# LORA.net
KiCad netlist of a schematic drawn in Altium Designer
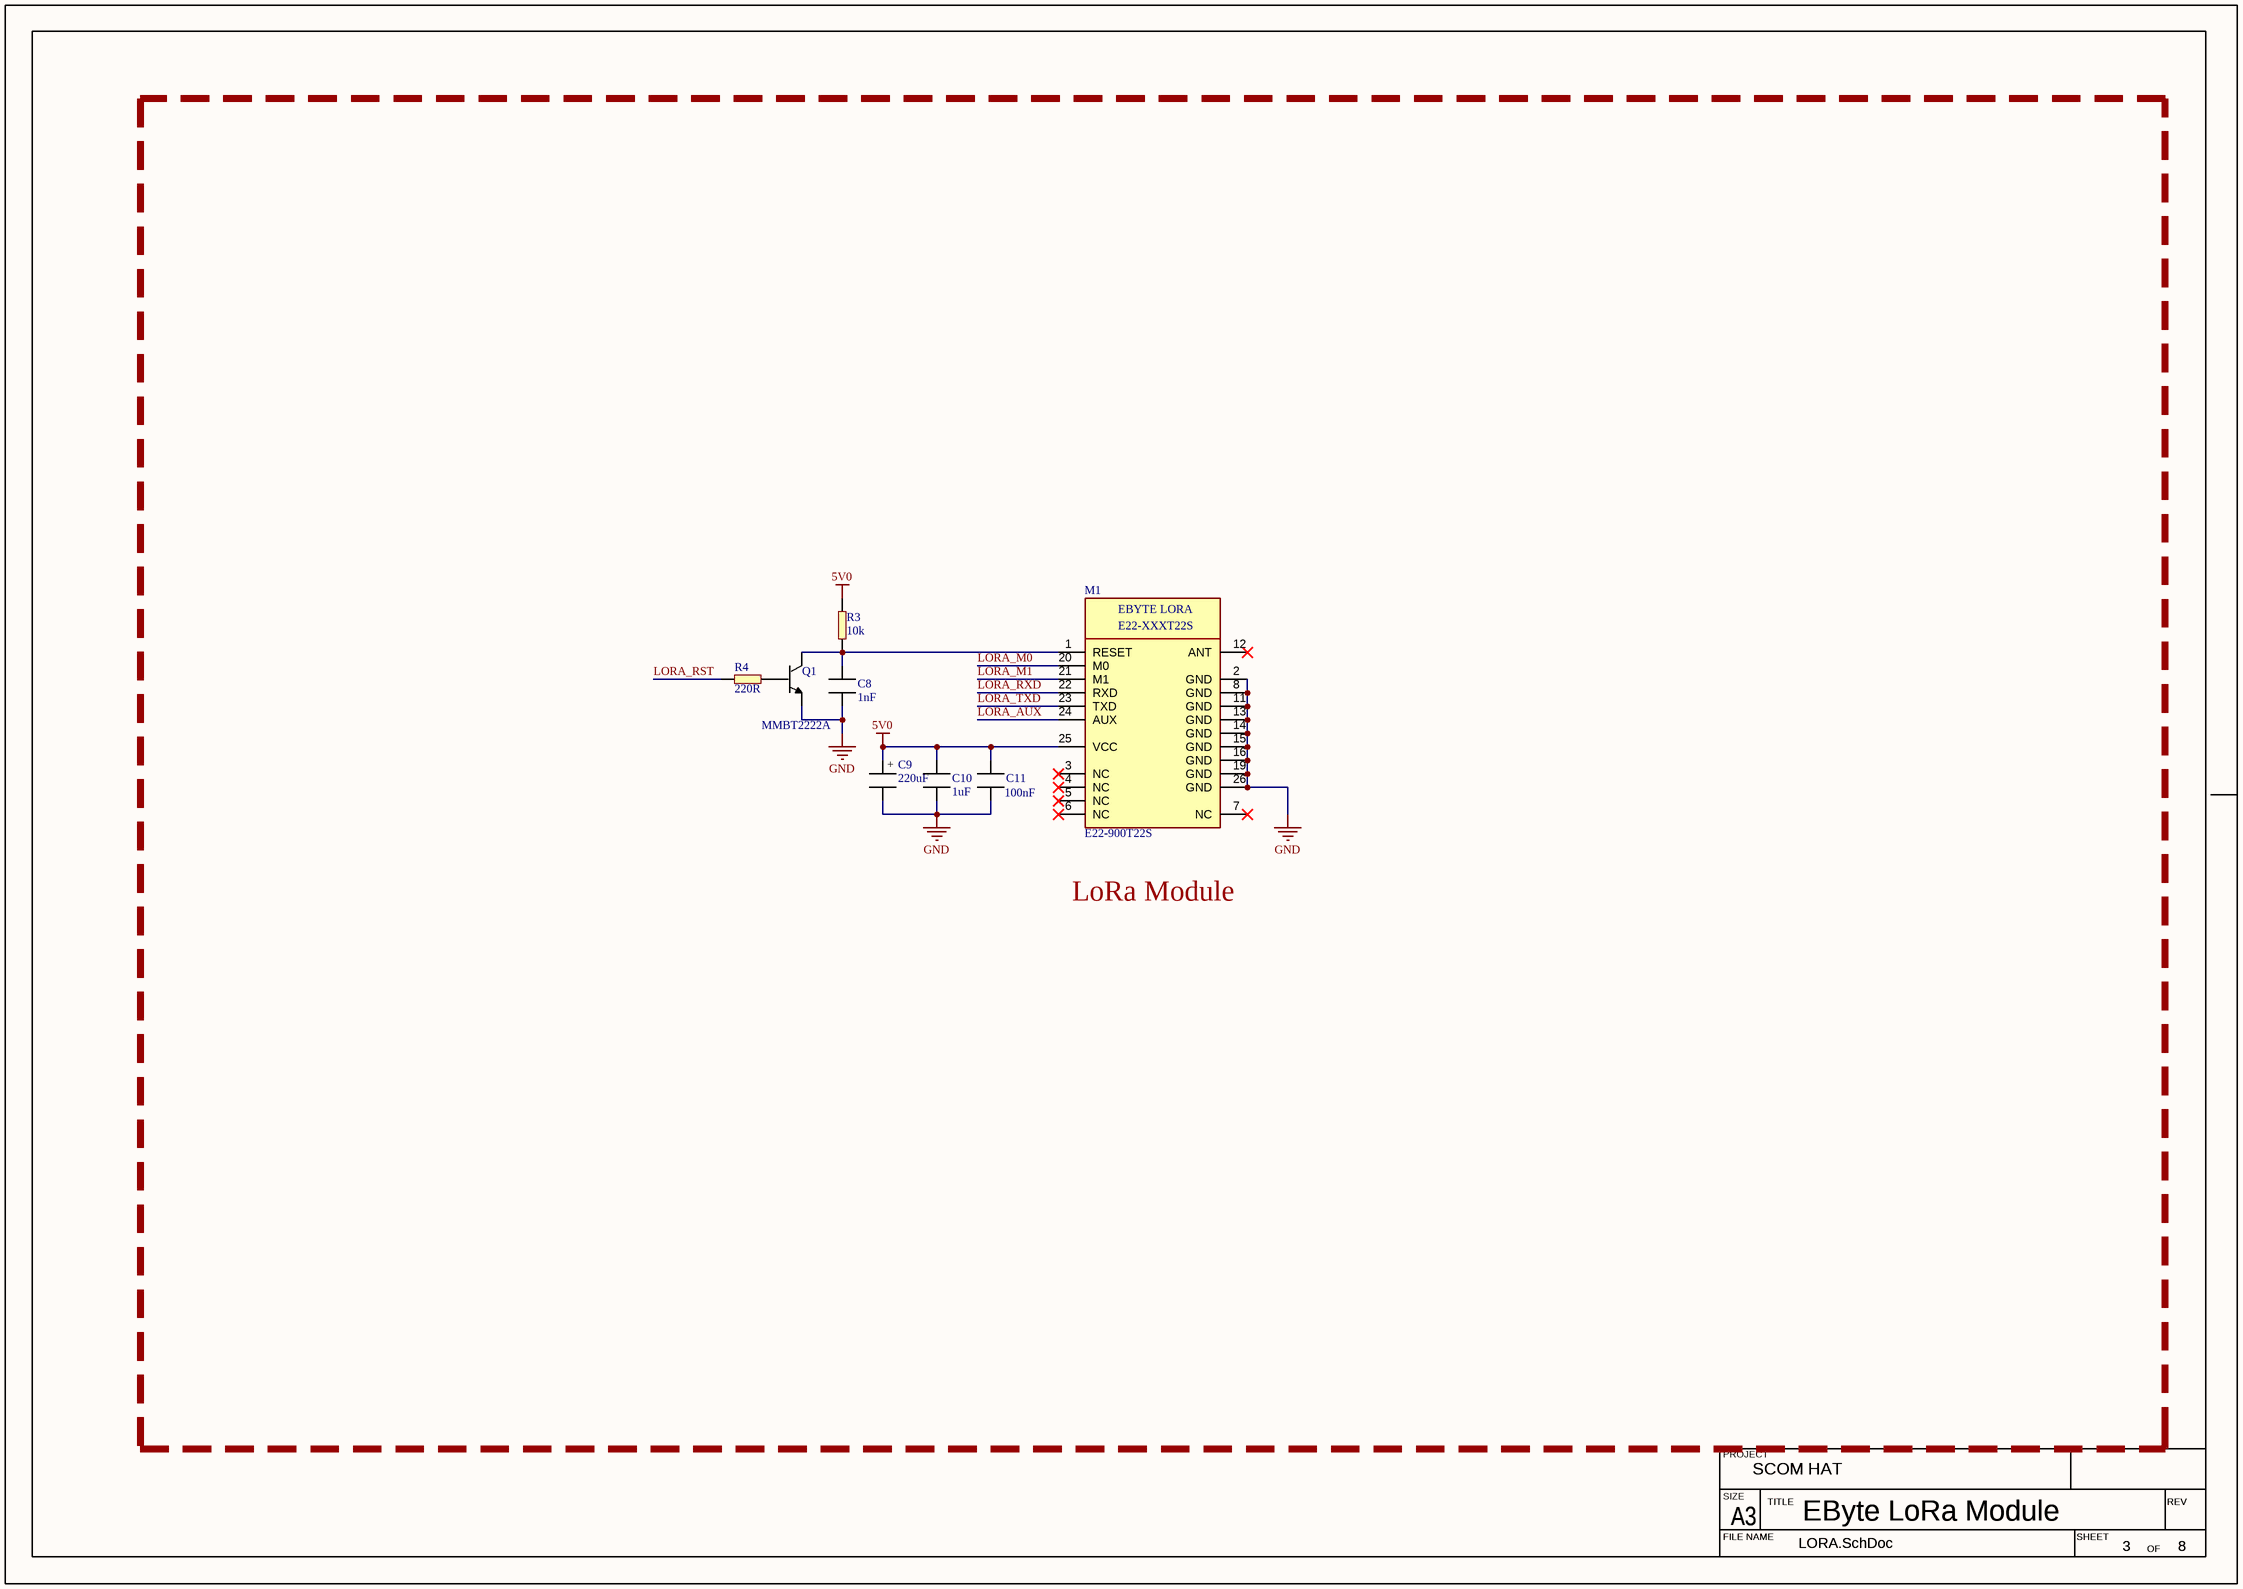
[diagram p0: LORA.SchDoc]

(export (version "E")
  (design (tool "Eeschema 10.0.6"))
  (components
    (comp (ref "C8")
      (value "1nF")
      (footprint "CAPC2012X13L")
      (description "Chip Capacitor, 2-Leads, Body 2.00x1.25mm, IPC High Density")
      (fields (field (name "Comment") "MLCC_0805"))
      (libsource (lib "Capacitor") (part "MLCC_0805"))
    )
    (comp (ref "C9")
      (value "220uF")
      (footprint "CAP_D10_H16_P5 - Flat")
      (description "Electrolytic Capacitor Through Hole D10 P5.0")
      (fields (field (name "Comment") "ERP_102-2"))
      (libsource (lib "ElectrolyticCapacitor") (part "CAP_D10_H16_P5"))
    )
    (comp (ref "C10")
      (value "1uF")
      (footprint "CAPC2012X13L")
      (description "Chip Capacitor, 2-Leads, Body 2.00x1.25mm, IPC High Density")
      (fields (field (name "Comment") "MLCC_0805"))
      (libsource (lib "Capacitor") (part "MLCC_0805"))
    )
    (comp (ref "C11")
      (value "100nF")
      (footprint "CAPC2012X13L")
      (description "Chip Capacitor, 2-Leads, Body 2.00x1.25mm, IPC High Density")
      (fields (field (name "Comment") "MLCC_0805"))
      (libsource (lib "Capacitor") (part "MLCC_0805"))
    )
    (comp (ref "M1")
      (value "E22-900T22S")
      (footprint "E22-XXXT22S")
      (description "E22 EByte LoRa Module")
      (fields (field (name "Comment") "E22-XXXT22S"))
      (libsource (lib "WirelessModule") (part "E22-XXXT22S"))
    )
    (comp (ref "Q1")
      (value "MMBT2222A")
      (footprint "MMBT2222")
      (fields (field (name "Comment") "ERP_105-1"))
      (libsource (lib "BJT") (part "MMBT2222"))
    )
    (comp (ref "R3")
      (value "10k")
      (footprint "RES_0603")
      (description "RES_0603")
      (fields (field (name "Comment") "ERP_101-1"))
      (libsource (lib "") (part "RES_0603_1"))
    )
    (comp (ref "R4")
      (value "220R")
      (footprint "RES_0603")
      (description "RES_0603")
      (fields (field (name "Comment") "ERP_101-1"))
      (libsource (lib "Resistor") (part "RES_0603"))
    )
  )
  (nets
    (net (code "1") (name "/LORA_AUX") (class "Default")
      (node (ref "M1") (pin "24") (pinfunction "AUX_24") (pintype "passive"))
    )
    (net (code "2") (name "/LORA_M0") (class "Default")
      (node (ref "M1") (pin "20") (pinfunction "M0_20") (pintype "passive"))
    )
    (net (code "3") (name "/LORA_M1") (class "Default")
      (node (ref "M1") (pin "21") (pinfunction "M1_21") (pintype "passive"))
    )
    (net (code "4") (name "/LORA_RST") (class "Default")
      (node (ref "R4") (pin "2") (pinfunction "2_2") (pintype "passive"))
    )
    (net (code "5") (name "/LORA_RXD") (class "Default")
      (node (ref "M1") (pin "22") (pinfunction "RXD_22") (pintype "passive"))
    )
    (net (code "6") (name "/LORA_TXD") (class "Default")
      (node (ref "M1") (pin "23") (pinfunction "TXD_23") (pintype "passive"))
    )
    (net (code "7") (name "5V0") (class "Default")
      (node (ref "C10") (pin "1") (pinfunction "1_1") (pintype "passive"))
      (node (ref "C11") (pin "1") (pinfunction "1_1") (pintype "passive"))
      (node (ref "C9") (pin "1") (pinfunction "1_1") (pintype "passive"))
      (node (ref "M1") (pin "25") (pinfunction "VCC_25") (pintype "passive"))
      (node (ref "R3") (pin "2") (pinfunction "2_2") (pintype "passive"))
    )
    (net (code "8") (name "GND") (class "Default")
      (node (ref "C10") (pin "2") (pinfunction "2_2") (pintype "passive"))
      (node (ref "C11") (pin "2") (pinfunction "2_2") (pintype "passive"))
      (node (ref "C8") (pin "2") (pinfunction "2_2") (pintype "passive"))
      (node (ref "C9") (pin "2") (pinfunction "2_2") (pintype "passive"))
      (node (ref "M1") (pin "11") (pinfunction "GND_11") (pintype "passive"))
      (node (ref "M1") (pin "13") (pinfunction "GND_13") (pintype "passive"))
      (node (ref "M1") (pin "14") (pinfunction "GND_14") (pintype "passive"))
      (node (ref "M1") (pin "15") (pinfunction "GND_15") (pintype "passive"))
      (node (ref "M1") (pin "16") (pinfunction "GND_16") (pintype "passive"))
      (node (ref "M1") (pin "19") (pinfunction "GND_19") (pintype "passive"))
      (node (ref "M1") (pin "2") (pinfunction "GND_2") (pintype "passive"))
      (node (ref "M1") (pin "26") (pinfunction "GND_26") (pintype "passive"))
      (node (ref "M1") (pin "8") (pinfunction "GND_8") (pintype "passive"))
      (node (ref "Q1") (pin "2") (pinfunction "2_2") (pintype "passive"))
    )
    (net (code "9") (name "Net-(M1-RESET)") (class "Default")
      (node (ref "C8") (pin "1") (pinfunction "1_1") (pintype "passive"))
      (node (ref "M1") (pin "1") (pinfunction "RESET_1") (pintype "passive"))
      (node (ref "Q1") (pin "3") (pinfunction "3_3") (pintype "passive"))
      (node (ref "R3") (pin "1") (pinfunction "1_1") (pintype "passive"))
    )
    (net (code "10") (name "Net-(Q1-Pad1)") (class "Default")
      (node (ref "Q1") (pin "1") (pinfunction "1_1") (pintype "passive"))
      (node (ref "R4") (pin "1") (pinfunction "1_1") (pintype "passive"))
    )
    (net (code "11") (name "unconnected-(M1-ANT-Pad12)") (class "Default")
      (node (ref "M1") (pin "12") (pinfunction "ANT_12") (pintype "passive+no_connect"))
    )
    (net (code "12") (name "unconnected-(M1-NC-Pad3)") (class "Default")
      (node (ref "M1") (pin "3") (pinfunction "NC_3") (pintype "passive+no_connect"))
    )
    (net (code "13") (name "unconnected-(M1-NC-Pad4)") (class "Default")
      (node (ref "M1") (pin "4") (pinfunction "NC_4") (pintype "passive+no_connect"))
    )
    (net (code "14") (name "unconnected-(M1-NC-Pad5)") (class "Default")
      (node (ref "M1") (pin "5") (pinfunction "NC_5") (pintype "passive+no_connect"))
    )
    (net (code "15") (name "unconnected-(M1-NC-Pad6)") (class "Default")
      (node (ref "M1") (pin "6") (pinfunction "NC_6") (pintype "passive+no_connect"))
    )
    (net (code "16") (name "unconnected-(M1-NC-Pad7)") (class "Default")
      (node (ref "M1") (pin "7") (pinfunction "NC_7") (pintype "passive+no_connect"))
    )
  )
)
